# shield.net
KiCad netlist of a schematic drawn in EAGLE
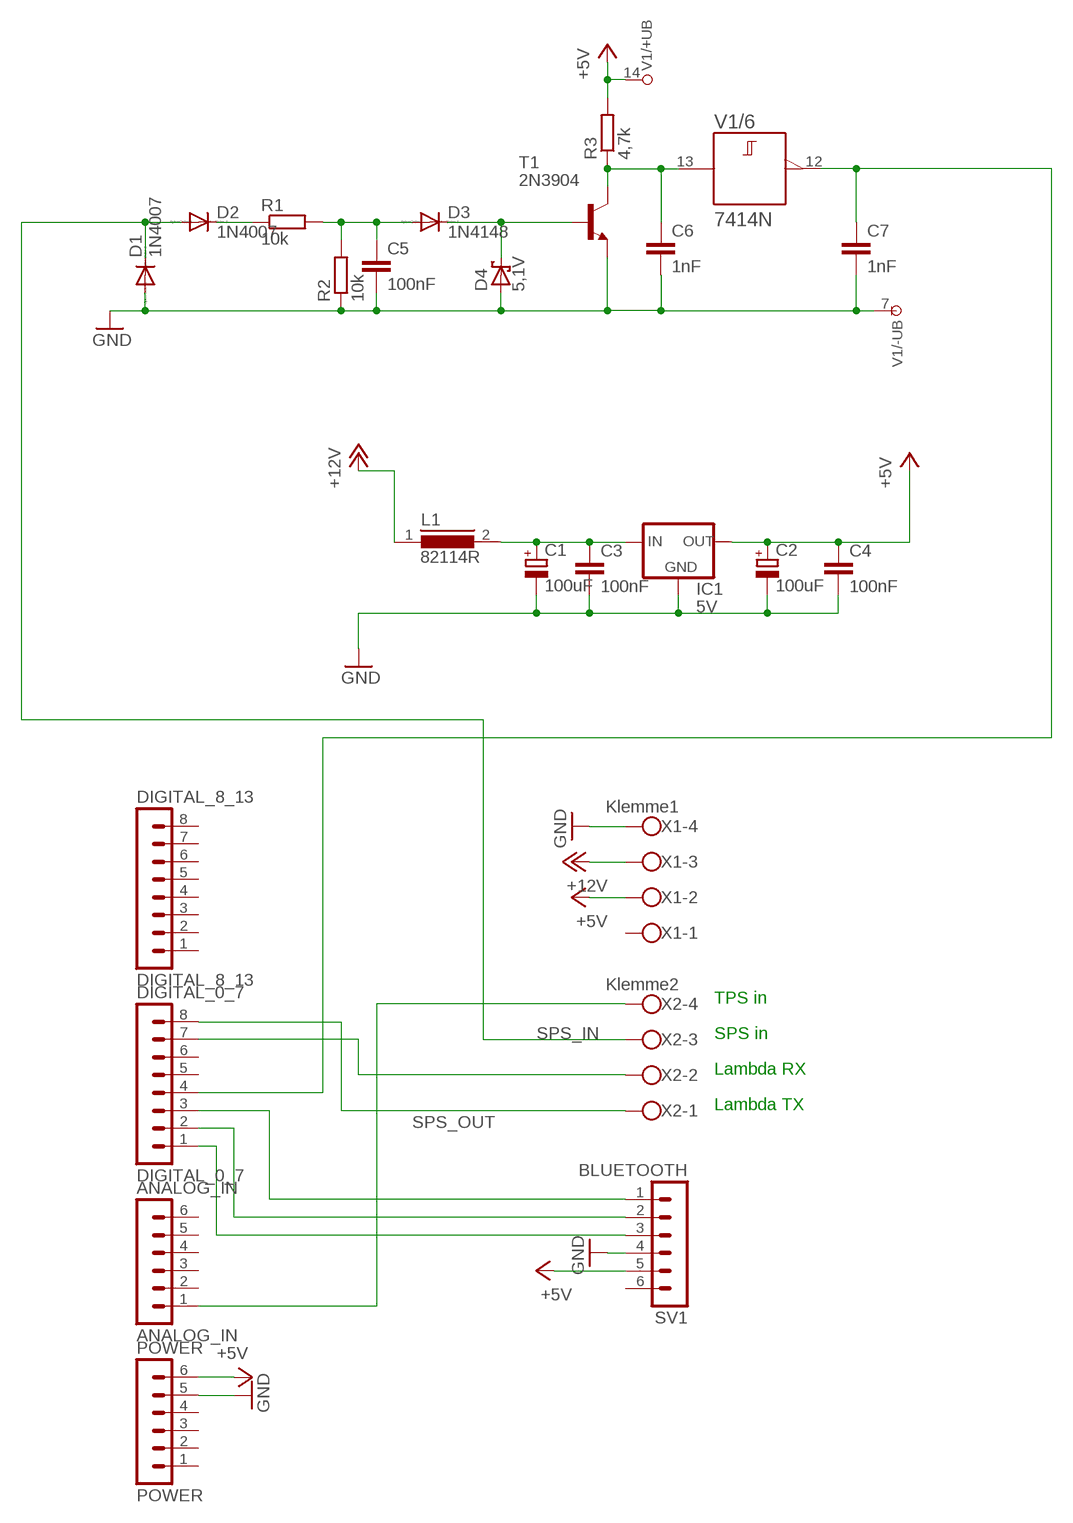
[diagram p0: schematic, sheet 1]

(export (version "E")
  (design (tool "Eeschema 10.0.6"))
  (components
    (comp (ref "ANALOG_IN")
      (value "ANALOG_IN")
      (footprint "eagle-import:MA06-1")
      (libsource (lib "eagle-import") (part "MA06-1"))
    )
    (comp (ref "C1")
      (value "100uF")
      (footprint "eagle-import:E2-4")
      (libsource (lib "eagle-import") (part "CPOL-EUE2-4"))
    )
    (comp (ref "C2")
      (value "100uF")
      (footprint "eagle-import:E2-4")
      (libsource (lib "eagle-import") (part "CPOL-EUE2-4"))
    )
    (comp (ref "C3")
      (value "100nF")
      (footprint "eagle-import:C050-035X075")
      (libsource (lib "eagle-import") (part "C-EU050-035X075"))
    )
    (comp (ref "C4")
      (value "100nF")
      (footprint "eagle-import:C050-035X075")
      (libsource (lib "eagle-import") (part "C-EU050-035X075"))
    )
    (comp (ref "C5")
      (value "100nF")
      (footprint "eagle-import:C075-032X103")
      (libsource (lib "eagle-import") (part "C-EU075-032X103"))
    )
    (comp (ref "C6")
      (value "1nF")
      (footprint "eagle-import:C075-032X103")
      (libsource (lib "eagle-import") (part "C-EU075-032X103"))
    )
    (comp (ref "C7")
      (value "1nF")
      (footprint "eagle-import:C075-032X103")
      (libsource (lib "eagle-import") (part "C-EU075-032X103"))
    )
    (comp (ref "D1")
      (value "1N4007")
      (footprint "eagle-import:D-5")
      (libsource (lib "eagle-import") (part "DIODE-D-5"))
    )
    (comp (ref "D2")
      (value "1N4007")
      (footprint "eagle-import:D-5")
      (libsource (lib "eagle-import") (part "DIODE-D-5"))
    )
    (comp (ref "D3")
      (value "1N4148")
      (footprint "eagle-import:D-5")
      (libsource (lib "eagle-import") (part "DIODE-D-5"))
    )
    (comp (ref "D4")
      (value "5,1V")
      (footprint "eagle-import:DO35-7")
      (libsource (lib "eagle-import") (part "SCHOTTKY-DIODEDO35-7"))
    )
    (comp (ref "DIGITAL_0_7")
      (value "DIGITAL_0_7")
      (footprint "eagle-import:MA08-1")
      (libsource (lib "eagle-import") (part "MA08-1"))
    )
    (comp (ref "DIGITAL_8_13")
      (value "DIGITAL_8_13")
      (footprint "eagle-import:MA08-1")
      (libsource (lib "eagle-import") (part "MA08-1"))
    )
    (comp (ref "IC1")
      (value "5V")
      (footprint "eagle-import:78XXS")
      (libsource (lib "eagle-import") (part "78XXS"))
    )
    (comp (ref "L1")
      (value "82114R")
      (footprint "eagle-import:82114R")
      (libsource (lib "eagle-import") (part "82114R"))
    )
    (comp (ref "POWER")
      (value "POWER")
      (footprint "eagle-import:MA06-1")
      (libsource (lib "eagle-import") (part "MA06-1"))
    )
    (comp (ref "R1")
      (value "10k")
      (footprint "eagle-import:0204_5")
      (libsource (lib "eagle-import") (part "R-EU_0204/5"))
    )
    (comp (ref "R2")
      (value "10k")
      (footprint "eagle-import:0204_5")
      (libsource (lib "eagle-import") (part "R-EU_0204/5"))
    )
    (comp (ref "R3")
      (value "4,7k")
      (footprint "eagle-import:0204_5")
      (libsource (lib "eagle-import") (part "R-EU_0204/5"))
    )
    (comp (ref "SV1")
      (value "BLUETOOTH")
      (footprint "eagle-import:MA06-1")
      (libsource (lib "eagle-import") (part "MA06-1"))
    )
    (comp (ref "T1")
      (value "2N3904")
      (footprint "eagle-import:TO92")
      (libsource (lib "eagle-import") (part "2N3904"))
    )
    (comp (ref "V1")
      (value "7414N")
      (footprint "eagle-import:DIL14")
      (libsource (lib "eagle-import") (part "7414N"))
    )
    (comp (ref "X1")
      (value "Klemme1")
      (footprint "eagle-import:W237-4")
      (libsource (lib "eagle-import") (part "W237-4"))
    )
    (comp (ref "X2")
      (value "Klemme2")
      (footprint "eagle-import:W237-4")
      (libsource (lib "eagle-import") (part "W237-4"))
    )
  )
  (nets
    (net (code "1") (name "+5V") (class "Default")
      (node (ref "C2") (pin "+") (pinfunction "+_+") (pintype "passive"))
      (node (ref "C4") (pin "1") (pinfunction "1_1") (pintype "passive"))
      (node (ref "IC1") (pin "OUT") (pinfunction "OUT_OUT") (pintype "passive"))
      (node (ref "POWER") (pin "6") (pinfunction "6_6") (pintype "passive"))
      (node (ref "R3") (pin "2") (pinfunction "2_2") (pintype "passive"))
      (node (ref "SV1") (pin "5") (pinfunction "5_5") (pintype "passive"))
      (node (ref "V1") (pin "14") (pinfunction "+UB_14") (pintype "power_in"))
      (node (ref "X1") (pin "2") (pinfunction "KL_2") (pintype "passive"))
    )
    (net (code "2") (name "+12V") (class "Default")
      (node (ref "L1") (pin "1") (pinfunction "1_1") (pintype "passive"))
      (node (ref "X1") (pin "3") (pinfunction "KL_3") (pintype "passive"))
    )
    (net (code "3") (name "/SPS_IN") (class "Default")
      (node (ref "D1") (pin "C") (pinfunction "C_C") (pintype "passive"))
      (node (ref "D2") (pin "A") (pinfunction "A_A") (pintype "passive"))
      (node (ref "X2") (pin "3") (pinfunction "KL_3") (pintype "passive"))
    )
    (net (code "4") (name "/SPS_OUT") (class "Default")
      (node (ref "C7") (pin "1") (pinfunction "1_1") (pintype "passive"))
      (node (ref "DIGITAL_0_7") (pin "4") (pinfunction "4_4") (pintype "passive"))
      (node (ref "V1") (pin "12") (pinfunction "Y_12") (pintype "output"))
    )
    (net (code "5") (name "GND") (class "Default")
      (node (ref "C1") (pin "-") (pinfunction "-_-") (pintype "passive"))
      (node (ref "C2") (pin "-") (pinfunction "-_-") (pintype "passive"))
      (node (ref "C3") (pin "2") (pinfunction "2_2") (pintype "passive"))
      (node (ref "C4") (pin "2") (pinfunction "2_2") (pintype "passive"))
      (node (ref "C5") (pin "2") (pinfunction "2_2") (pintype "passive"))
      (node (ref "C6") (pin "2") (pinfunction "2_2") (pintype "passive"))
      (node (ref "C7") (pin "2") (pinfunction "2_2") (pintype "passive"))
      (node (ref "D1") (pin "A") (pinfunction "A_A") (pintype "passive"))
      (node (ref "D4") (pin "A") (pinfunction "A_A") (pintype "passive"))
      (node (ref "IC1") (pin "GND") (pinfunction "GND_GND") (pintype "input"))
      (node (ref "POWER") (pin "5") (pinfunction "5_5") (pintype "passive"))
      (node (ref "R2") (pin "1") (pinfunction "1_1") (pintype "passive"))
      (node (ref "SV1") (pin "4") (pinfunction "4_4") (pintype "passive"))
      (node (ref "T1") (pin "3") (pinfunction "E_3") (pintype "passive"))
      (node (ref "V1") (pin "7") (pinfunction "-UB_7") (pintype "power_in"))
      (node (ref "X1") (pin "4") (pinfunction "KL_4") (pintype "passive"))
    )
    (net (code "6") (name "Net-(C1-Pad+)") (class "Default")
      (node (ref "C1") (pin "+") (pinfunction "+_+") (pintype "passive"))
      (node (ref "C3") (pin "1") (pinfunction "1_1") (pintype "passive"))
      (node (ref "IC1") (pin "IN") (pinfunction "IN_IN") (pintype "input"))
      (node (ref "L1") (pin "2") (pinfunction "2_2") (pintype "passive"))
    )
    (net (code "7") (name "Net-(C5-Pad1)") (class "Default")
      (node (ref "C5") (pin "1") (pinfunction "1_1") (pintype "passive"))
      (node (ref "D3") (pin "A") (pinfunction "A_A") (pintype "passive"))
      (node (ref "R1") (pin "2") (pinfunction "2_2") (pintype "passive"))
      (node (ref "R2") (pin "2") (pinfunction "2_2") (pintype "passive"))
    )
    (net (code "8") (name "Net-(D2-PadC)") (class "Default")
      (node (ref "D2") (pin "C") (pinfunction "C_C") (pintype "passive"))
      (node (ref "R1") (pin "1") (pinfunction "1_1") (pintype "passive"))
    )
    (net (code "9") (name "Net-(DIGITAL_0_7-Pad1)") (class "Default")
      (node (ref "DIGITAL_0_7") (pin "1") (pinfunction "1_1") (pintype "passive"))
      (node (ref "SV1") (pin "3") (pinfunction "3_3") (pintype "passive"))
    )
    (net (code "10") (name "Net-(DIGITAL_0_7-Pad2)") (class "Default")
      (node (ref "DIGITAL_0_7") (pin "2") (pinfunction "2_2") (pintype "passive"))
      (node (ref "SV1") (pin "2") (pinfunction "2_2") (pintype "passive"))
    )
    (net (code "11") (name "Net-(DIGITAL_0_7-Pad3)") (class "Default")
      (node (ref "DIGITAL_0_7") (pin "3") (pinfunction "3_3") (pintype "passive"))
      (node (ref "SV1") (pin "1") (pinfunction "1_1") (pintype "passive"))
    )
    (net (code "12") (name "Net-(T1-B)") (class "Default")
      (node (ref "D3") (pin "C") (pinfunction "C_C") (pintype "passive"))
      (node (ref "D4") (pin "C") (pinfunction "C_C") (pintype "passive"))
      (node (ref "T1") (pin "2") (pinfunction "B_2") (pintype "passive"))
    )
    (net (code "13") (name "Net-(T1-C)") (class "Default")
      (node (ref "C6") (pin "1") (pinfunction "1_1") (pintype "passive"))
      (node (ref "R3") (pin "1") (pinfunction "1_1") (pintype "passive"))
      (node (ref "T1") (pin "1") (pinfunction "C_1") (pintype "passive"))
      (node (ref "V1") (pin "13") (pinfunction "A_13") (pintype "input"))
    )
    (net (code "14") (name "Net-(X2A-KL)") (class "Default")
      (node (ref "DIGITAL_0_7") (pin "8") (pinfunction "8_8") (pintype "passive"))
      (node (ref "X2") (pin "1") (pinfunction "KL_1") (pintype "passive"))
    )
    (net (code "15") (name "Net-(X2B-KL)") (class "Default")
      (node (ref "DIGITAL_0_7") (pin "7") (pinfunction "7_7") (pintype "passive"))
      (node (ref "X2") (pin "2") (pinfunction "KL_2") (pintype "passive"))
    )
    (net (code "16") (name "Net-(X2D-KL)") (class "Default")
      (node (ref "ANALOG_IN") (pin "1") (pinfunction "1_1") (pintype "passive"))
      (node (ref "X2") (pin "4") (pinfunction "KL_4") (pintype "passive"))
    )
    (net (code "17") (name "unconnected-(ANALOG_IN-Pad2)") (class "Default")
      (node (ref "ANALOG_IN") (pin "2") (pinfunction "2_2") (pintype "passive"))
    )
    (net (code "18") (name "unconnected-(ANALOG_IN-Pad3)") (class "Default")
      (node (ref "ANALOG_IN") (pin "3") (pinfunction "3_3") (pintype "passive"))
    )
    (net (code "19") (name "unconnected-(ANALOG_IN-Pad4)") (class "Default")
      (node (ref "ANALOG_IN") (pin "4") (pinfunction "4_4") (pintype "passive"))
    )
    (net (code "20") (name "unconnected-(ANALOG_IN-Pad5)") (class "Default")
      (node (ref "ANALOG_IN") (pin "5") (pinfunction "5_5") (pintype "passive"))
    )
    (net (code "21") (name "unconnected-(ANALOG_IN-Pad6)") (class "Default")
      (node (ref "ANALOG_IN") (pin "6") (pinfunction "6_6") (pintype "passive"))
    )
    (net (code "22") (name "unconnected-(DIGITAL_0_7-Pad5)") (class "Default")
      (node (ref "DIGITAL_0_7") (pin "5") (pinfunction "5_5") (pintype "passive"))
    )
    (net (code "23") (name "unconnected-(DIGITAL_0_7-Pad6)") (class "Default")
      (node (ref "DIGITAL_0_7") (pin "6") (pinfunction "6_6") (pintype "passive"))
    )
    (net (code "24") (name "unconnected-(DIGITAL_8_13-Pad1)") (class "Default")
      (node (ref "DIGITAL_8_13") (pin "1") (pinfunction "1_1") (pintype "passive"))
    )
    (net (code "25") (name "unconnected-(DIGITAL_8_13-Pad2)") (class "Default")
      (node (ref "DIGITAL_8_13") (pin "2") (pinfunction "2_2") (pintype "passive"))
    )
    (net (code "26") (name "unconnected-(DIGITAL_8_13-Pad3)") (class "Default")
      (node (ref "DIGITAL_8_13") (pin "3") (pinfunction "3_3") (pintype "passive"))
    )
    (net (code "27") (name "unconnected-(DIGITAL_8_13-Pad4)") (class "Default")
      (node (ref "DIGITAL_8_13") (pin "4") (pinfunction "4_4") (pintype "passive"))
    )
    (net (code "28") (name "unconnected-(DIGITAL_8_13-Pad5)") (class "Default")
      (node (ref "DIGITAL_8_13") (pin "5") (pinfunction "5_5") (pintype "passive"))
    )
    (net (code "29") (name "unconnected-(DIGITAL_8_13-Pad6)") (class "Default")
      (node (ref "DIGITAL_8_13") (pin "6") (pinfunction "6_6") (pintype "passive"))
    )
    (net (code "30") (name "unconnected-(DIGITAL_8_13-Pad7)") (class "Default")
      (node (ref "DIGITAL_8_13") (pin "7") (pinfunction "7_7") (pintype "passive"))
    )
    (net (code "31") (name "unconnected-(DIGITAL_8_13-Pad8)") (class "Default")
      (node (ref "DIGITAL_8_13") (pin "8") (pinfunction "8_8") (pintype "passive"))
    )
    (net (code "32") (name "unconnected-(POWER-Pad1)") (class "Default")
      (node (ref "POWER") (pin "1") (pinfunction "1_1") (pintype "passive"))
    )
    (net (code "33") (name "unconnected-(POWER-Pad2)") (class "Default")
      (node (ref "POWER") (pin "2") (pinfunction "2_2") (pintype "passive"))
    )
    (net (code "34") (name "unconnected-(POWER-Pad3)") (class "Default")
      (node (ref "POWER") (pin "3") (pinfunction "3_3") (pintype "passive"))
    )
    (net (code "35") (name "unconnected-(POWER-Pad4)") (class "Default")
      (node (ref "POWER") (pin "4") (pinfunction "4_4") (pintype "passive"))
    )
    (net (code "36") (name "unconnected-(SV1-Pad6)") (class "Default")
      (node (ref "SV1") (pin "6") (pinfunction "6_6") (pintype "passive"))
    )
    (net (code "37") (name "unconnected-(X1A-KL-Pad1)") (class "Default")
      (node (ref "X1") (pin "1") (pinfunction "KL_1") (pintype "passive"))
    )
  )
)
